# Sheet1.net
KiCad netlist of a schematic drawn in Altium Designer
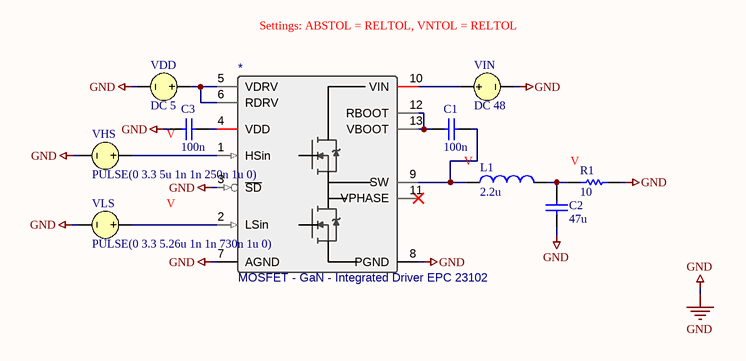
[diagram p0: Sheet1.SchDoc]

(export (version "E")
  (design (tool "Eeschema 10.0.6"))
  (components
    (comp (ref "*")
      (value "MOSFET - GaN - Integrated Driver EPC 23102")
      (footprint "QFN-13_EPC_EPC2310X")
      (libsource (lib "EE490") (part "MOSFET - GaN - Integrated Driver EPC 23102"))
    )
    (comp (ref "C1")
      (value "100n")
      (description "Capacitor")
      (libsource (lib "Simulation Generic Components") (part "Capacitor"))
    )
    (comp (ref "C2")
      (value "47u")
      (description "Capacitor")
      (libsource (lib "Simulation Generic Components") (part "Capacitor"))
    )
    (comp (ref "C3")
      (value "100n")
      (description "Capacitor")
      (libsource (lib "Simulation Generic Components") (part "Capacitor"))
    )
    (comp (ref "L1")
      (value "2.2u")
      (description "Inductor")
      (libsource (lib "Simulation Generic Components") (part "Inductor"))
    )
    (comp (ref "R1")
      (value "10")
      (description "Resistor")
      (libsource (lib "Simulation Generic Components") (part "Resistor"))
    )
    (comp (ref "VDD")
      (value "DC 5")
      (description "Voltage Source")
      (fields (field (name "PUBLISHER") "Altium Limited"))
      (libsource (lib "Simulation Generic Components") (part "VSRC"))
    )
    (comp (ref "VHS")
      (value "PULSE(0 3.3 5u 1n 1n 250n 1u 0)")
      (description "Voltage Source")
      (fields (field (name "PUBLISHER") "Altium Limited"))
      (libsource (lib "Simulation Generic Components") (part "VSRC"))
    )
    (comp (ref "VIN")
      (value "DC 48")
      (description "Voltage Source")
      (fields (field (name "PUBLISHER") "Altium Limited"))
      (libsource (lib "Simulation Generic Components") (part "VSRC"))
    )
    (comp (ref "VLS")
      (value "PULSE(0 3.3 5.26u 1n 1n 730n 1u 0)")
      (description "Voltage Source")
      (fields (field (name "PUBLISHER") "Altium Limited"))
      (libsource (lib "Simulation Generic Components") (part "VSRC"))
    )
  )
  (nets
    (net (code "1") (name "GND") (class "Default")
      (node (ref "*") (pin "3") (pinfunction "~{SD}_3") (pintype "input"))
      (node (ref "*") (pin "7") (pinfunction "AGND_7") (pintype "power_in"))
      (node (ref "*") (pin "8") (pinfunction "PGND_8") (pintype "power_in"))
      (node (ref "C2") (pin "1") (pinfunction "1_1") (pintype "passive"))
      (node (ref "C3") (pin "1") (pinfunction "1_1") (pintype "passive"))
      (node (ref "R1") (pin "2") (pinfunction "2_2") (pintype "passive"))
      (node (ref "VDD") (pin "2") (pinfunction "2_2") (pintype "passive"))
      (node (ref "VHS") (pin "2") (pinfunction "2_2") (pintype "passive"))
      (node (ref "VIN") (pin "2") (pinfunction "2_2") (pintype "passive"))
      (node (ref "VLS") (pin "2") (pinfunction "2_2") (pintype "passive"))
    )
    (net (code "2") (name "Net-(*-HSin)") (class "Default")
      (node (ref "*") (pin "1") (pinfunction "HSin_1") (pintype "input"))
      (node (ref "VHS") (pin "1") (pinfunction "1_1") (pintype "passive"))
    )
    (net (code "3") (name "Net-(*-LSin)") (class "Default")
      (node (ref "*") (pin "2") (pinfunction "LSin_2") (pintype "input"))
      (node (ref "VLS") (pin "1") (pinfunction "1_1") (pintype "passive"))
    )
    (net (code "4") (name "Net-(*-RBOOT)") (class "Default")
      (node (ref "*") (pin "12") (pinfunction "RBOOT_12") (pintype "power_in"))
      (node (ref "*") (pin "13") (pinfunction "VBOOT_13") (pintype "power_in"))
      (node (ref "C1") (pin "1") (pinfunction "1_1") (pintype "passive"))
    )
    (net (code "5") (name "Net-(*-RDRV)") (class "Default")
      (node (ref "*") (pin "5") (pinfunction "VDRV_5") (pintype "power_in"))
      (node (ref "*") (pin "6") (pinfunction "RDRV_6") (pintype "power_in"))
      (node (ref "VDD") (pin "1") (pinfunction "1_1") (pintype "passive"))
    )
    (net (code "6") (name "Net-(*-SW)") (class "Default")
      (node (ref "*") (pin "9") (pinfunction "SW_9") (pintype "power_in"))
      (node (ref "C1") (pin "2") (pinfunction "2_2") (pintype "passive"))
      (node (ref "L1") (pin "1") (pinfunction "1_1") (pintype "passive"))
    )
    (net (code "7") (name "Net-(*-VDD)") (class "Default")
      (node (ref "*") (pin "4") (pinfunction "VDD_4") (pintype "power_in"))
      (node (ref "C3") (pin "2") (pinfunction "2_2") (pintype "passive"))
    )
    (net (code "8") (name "Net-(*-VIN)") (class "Default")
      (node (ref "*") (pin "10") (pinfunction "VIN_10") (pintype "power_in"))
      (node (ref "VIN") (pin "1") (pinfunction "1_1") (pintype "passive"))
    )
    (net (code "9") (name "Net-(C2-Pad2)") (class "Default")
      (node (ref "C2") (pin "2") (pinfunction "2_2") (pintype "passive"))
      (node (ref "L1") (pin "2") (pinfunction "2_2") (pintype "passive"))
      (node (ref "R1") (pin "1") (pinfunction "1_1") (pintype "passive"))
    )
    (net (code "10") (name "unconnected-(*-VPHASE-Pad11)") (class "Default")
      (node (ref "*") (pin "11") (pinfunction "VPHASE_11") (pintype "power_in+no_connect"))
    )
  )
)
